# MxxxCol.net
KiCad netlist of a schematic drawn in EAGLE
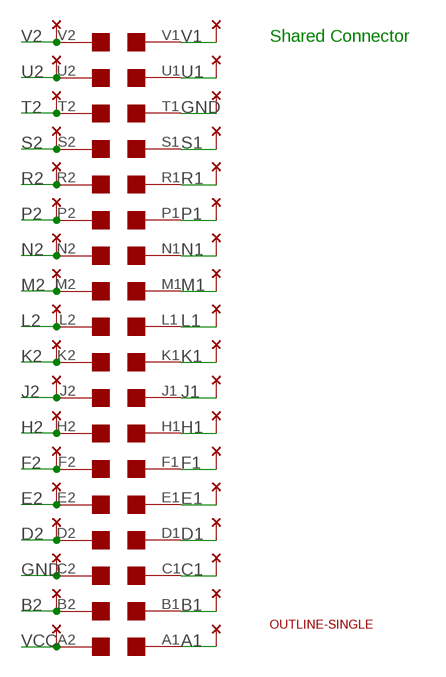
[diagram p0: schematic, sheet 1]
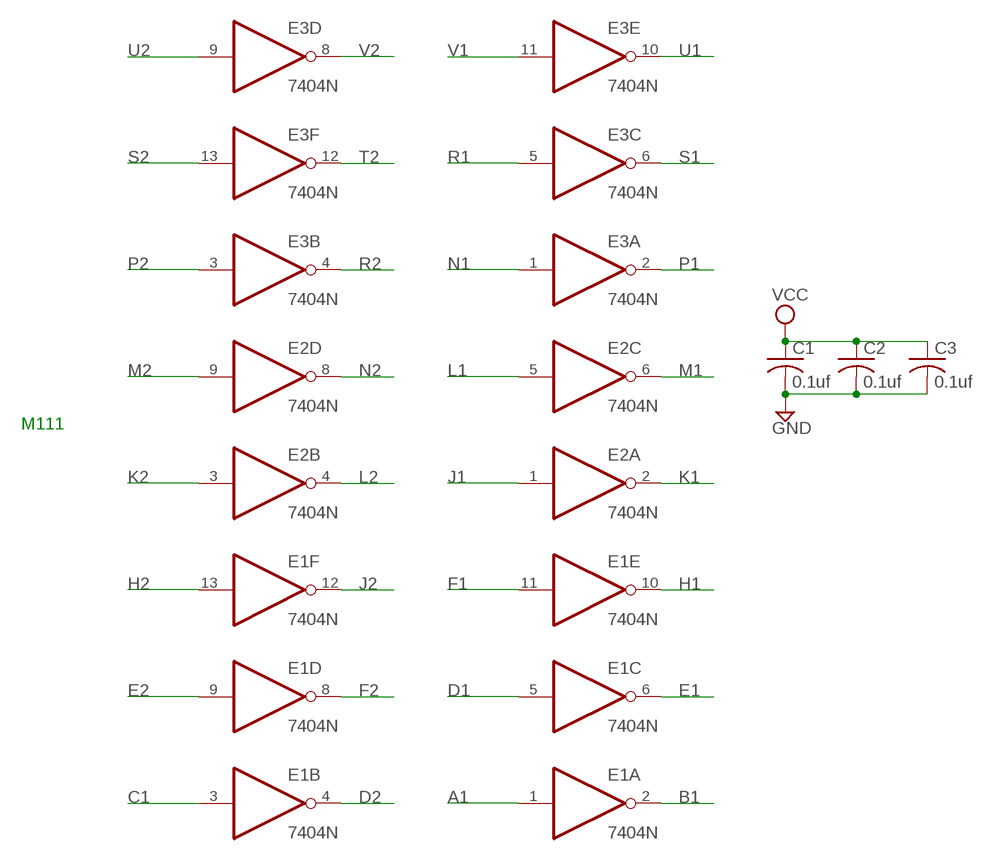
[diagram p1: schematic, sheet 2]
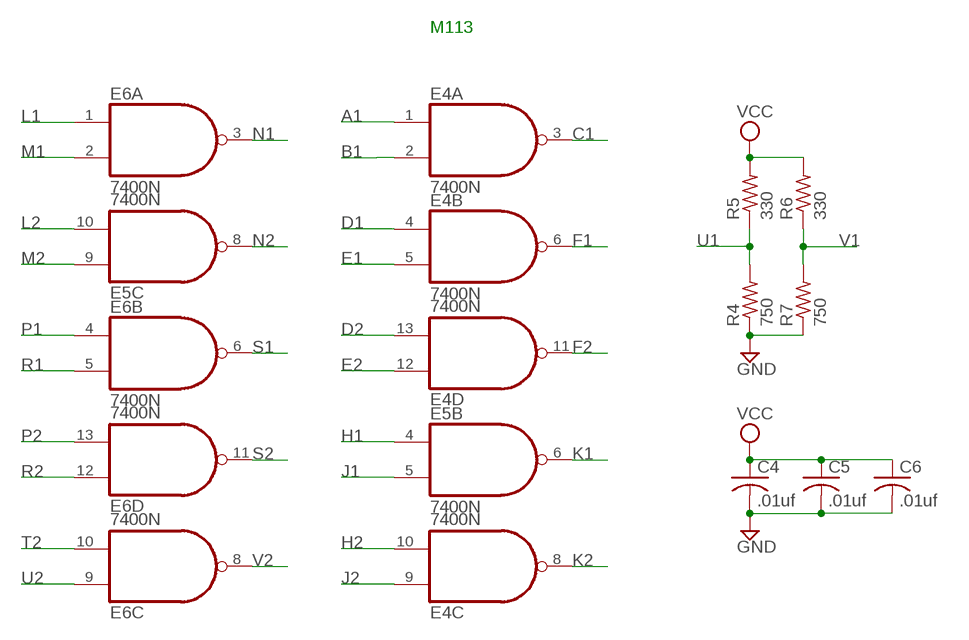
[diagram p2: schematic, sheet 3]
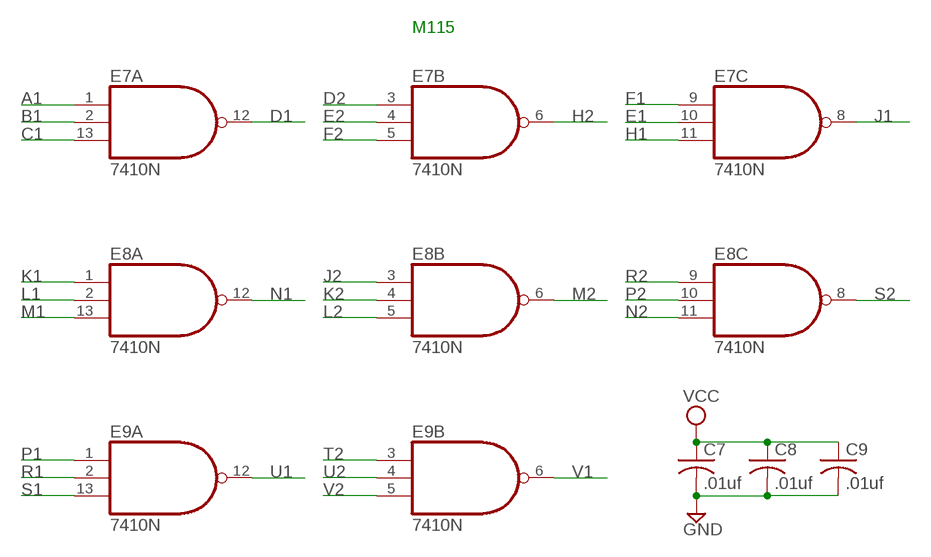
[diagram p3: schematic, sheet 4]
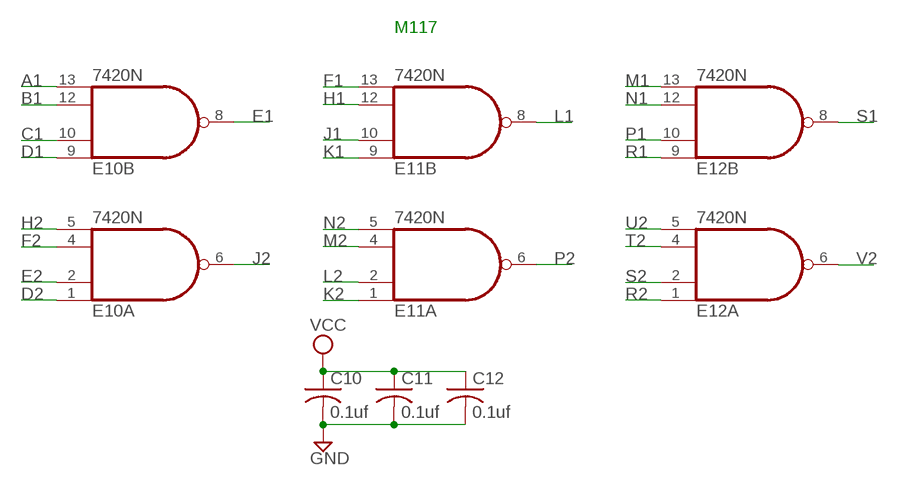
[diagram p4: schematic, sheet 5]
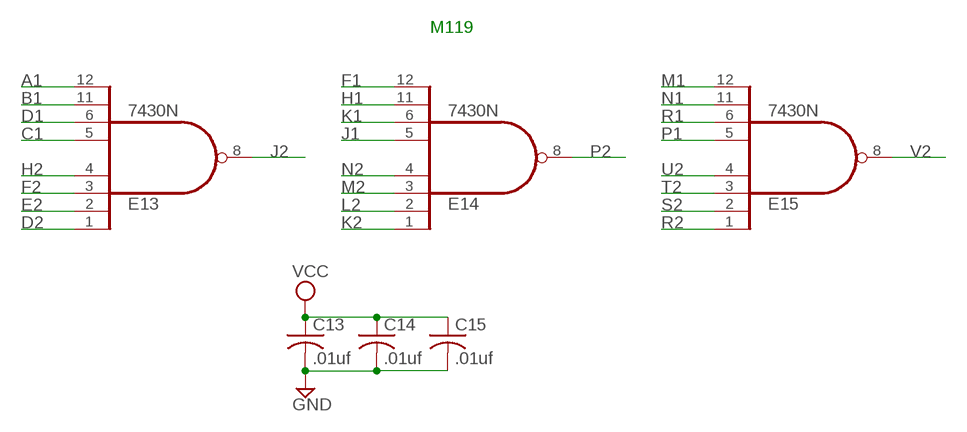
[diagram p5: schematic, sheet 6]

(export (version "E")
  (design (tool "Eeschema 10.0.6"))
  (components
    (comp (ref "U$1")
      (value "EDGE-2CONNECTOR")
      (footprint "eagle-import:EDGE-CON2")
      (libsource (lib "eagle-import") (part "EDGE-2CONNECTOR"))
    )
    (comp (ref "U$2")
      (value "OUTLINE-SINGLE")
      (footprint "eagle-import:SINGLE")
      (libsource (lib "eagle-import") (part "OUTLINE-SINGLE"))
    )
    (comp (ref "U$4")
      (value "THRU-HOLE2A")
      (footprint "eagle-import:THRU-HOLEA")
      (libsource (lib "eagle-import") (part "THRU-HOLE2A"))
    )
    (comp (ref "C7")
      (value ".01uf")
      (footprint "eagle-import:C050-025X075")
      (libsource (lib "eagle-import") (part "C-US050-025X075"))
    )
    (comp (ref "C8")
      (value ".01uf")
      (footprint "eagle-import:C050-025X075")
      (libsource (lib "eagle-import") (part "C-US050-025X075"))
    )
    (comp (ref "C9")
      (value ".01uf")
      (footprint "eagle-import:C050-025X075")
      (libsource (lib "eagle-import") (part "C-US050-025X075"))
    )
    (comp (ref "E7")
      (value "7410N")
      (footprint "eagle-import:DIL14")
      (libsource (lib "eagle-import") (part "7410N"))
    )
    (comp (ref "E8")
      (value "7410N")
      (footprint "eagle-import:DIL14")
      (libsource (lib "eagle-import") (part "7410N"))
    )
    (comp (ref "E9")
      (value "7410N")
      (footprint "eagle-import:DIL14")
      (libsource (lib "eagle-import") (part "7410N"))
    )
    (comp (ref "C4")
      (value ".01uf")
      (footprint "eagle-import:C050-025X075")
      (libsource (lib "eagle-import") (part "C-US050-025X075"))
    )
    (comp (ref "C5")
      (value ".01uf")
      (footprint "eagle-import:C050-025X075")
      (libsource (lib "eagle-import") (part "C-US050-025X075"))
    )
    (comp (ref "C6")
      (value ".01uf")
      (footprint "eagle-import:C050-025X075")
      (libsource (lib "eagle-import") (part "C-US050-025X075"))
    )
    (comp (ref "E4")
      (value "7400N")
      (footprint "eagle-import:DIL14")
      (libsource (lib "eagle-import") (part "7400N"))
    )
    (comp (ref "E5")
      (value "7400N")
      (footprint "eagle-import:DIL14")
      (libsource (lib "eagle-import") (part "7400N"))
    )
    (comp (ref "E6")
      (value "7400N")
      (footprint "eagle-import:DIL14")
      (libsource (lib "eagle-import") (part "7400N"))
    )
    (comp (ref "R4")
      (value "750")
      (footprint "eagle-import:0207_10")
      (libsource (lib "eagle-import") (part "R-US_0207/10"))
    )
    (comp (ref "R5")
      (value "330")
      (footprint "eagle-import:0207_10")
      (libsource (lib "eagle-import") (part "R-US_0207/10"))
    )
    (comp (ref "R6")
      (value "330")
      (footprint "eagle-import:0207_10")
      (libsource (lib "eagle-import") (part "R-US_0207/10"))
    )
    (comp (ref "R7")
      (value "750")
      (footprint "eagle-import:0207_10")
      (libsource (lib "eagle-import") (part "R-US_0207/10"))
    )
    (comp (ref "C13")
      (value ".01uf")
      (footprint "eagle-import:C050-025X075")
      (libsource (lib "eagle-import") (part "C-US050-025X075"))
    )
    (comp (ref "C14")
      (value ".01uf")
      (footprint "eagle-import:C050-025X075")
      (libsource (lib "eagle-import") (part "C-US050-025X075"))
    )
    (comp (ref "C15")
      (value ".01uf")
      (footprint "eagle-import:C050-025X075")
      (libsource (lib "eagle-import") (part "C-US050-025X075"))
    )
    (comp (ref "E13")
      (value "7430N")
      (footprint "eagle-import:DIL14")
      (libsource (lib "eagle-import") (part "7430N"))
    )
    (comp (ref "E14")
      (value "7430N")
      (footprint "eagle-import:DIL14")
      (libsource (lib "eagle-import") (part "7430N"))
    )
    (comp (ref "E15")
      (value "7430N")
      (footprint "eagle-import:DIL14")
      (libsource (lib "eagle-import") (part "7430N"))
    )
    (comp (ref "C1")
      (value "0.1uf")
      (footprint "eagle-import:C050-025X075")
      (libsource (lib "eagle-import") (part "C-US050-025X075"))
    )
    (comp (ref "C2")
      (value "0.1uf")
      (footprint "eagle-import:C050-025X075")
      (libsource (lib "eagle-import") (part "C-US050-025X075"))
    )
    (comp (ref "C3")
      (value "0.1uf")
      (footprint "eagle-import:C050-025X075")
      (libsource (lib "eagle-import") (part "C-US050-025X075"))
    )
    (comp (ref "E1")
      (value "7404N")
      (footprint "eagle-import:DIL14")
      (libsource (lib "eagle-import") (part "7404N"))
    )
    (comp (ref "E2")
      (value "7404N")
      (footprint "eagle-import:DIL14")
      (libsource (lib "eagle-import") (part "7404N"))
    )
    (comp (ref "E3")
      (value "7404N")
      (footprint "eagle-import:DIL14")
      (libsource (lib "eagle-import") (part "7404N"))
    )
    (comp (ref "C10")
      (value "0.1uf")
      (footprint "eagle-import:C050-025X075")
      (libsource (lib "eagle-import") (part "C-US050-025X075"))
    )
    (comp (ref "C11")
      (value "0.1uf")
      (footprint "eagle-import:C050-025X075")
      (libsource (lib "eagle-import") (part "C-US050-025X075"))
    )
    (comp (ref "C12")
      (value "0.1uf")
      (footprint "eagle-import:C050-025X075")
      (libsource (lib "eagle-import") (part "C-US050-025X075"))
    )
    (comp (ref "E10")
      (value "7420N")
      (footprint "eagle-import:DIL14")
      (libsource (lib "eagle-import") (part "7420NS"))
    )
    (comp (ref "E11")
      (value "7420N")
      (footprint "eagle-import:DIL14")
      (libsource (lib "eagle-import") (part "7420NS"))
    )
    (comp (ref "E12")
      (value "7420N")
      (footprint "eagle-import:DIL14")
      (libsource (lib "eagle-import") (part "7420NS"))
    )
  )
  (nets
    (net (code "1") (name "A1") (class "Default")
      (node (ref "E1") (pin "1") (pinfunction "I_1") (pintype "input"))
      (node (ref "E10") (pin "13") (pinfunction "I3_13") (pintype "input"))
      (node (ref "E13") (pin "12") (pinfunction "I7_12") (pintype "input"))
      (node (ref "E4") (pin "1") (pinfunction "I0_1") (pintype "input"))
      (node (ref "E7") (pin "1") (pinfunction "I0_1") (pintype "input"))
      (node (ref "U$1") (pin "A1") (pinfunction "1_A1") (pintype "bidirectional"))
      (node (ref "U$4") (pin "A1") (pinfunction "P$1_A1") (pintype "passive"))
    )
    (net (code "2") (name "B1") (class "Default")
      (node (ref "E1") (pin "2") (pinfunction "O_2") (pintype "output"))
      (node (ref "E10") (pin "12") (pinfunction "I2_12") (pintype "input"))
      (node (ref "E13") (pin "11") (pinfunction "I6_11") (pintype "input"))
      (node (ref "E4") (pin "2") (pinfunction "I1_2") (pintype "input"))
      (node (ref "E7") (pin "2") (pinfunction "I1_2") (pintype "input"))
      (node (ref "U$1") (pin "B1") (pinfunction "1_B1") (pintype "bidirectional"))
      (node (ref "U$4") (pin "B1") (pinfunction "P$1_B1") (pintype "passive"))
    )
    (net (code "3") (name "B2") (class "Default")
      (node (ref "U$1") (pin "B2") (pinfunction "1_B2") (pintype "bidirectional"))
      (node (ref "U$4") (pin "B2") (pinfunction "P$1_B2") (pintype "passive"))
    )
    (net (code "4") (name "C1") (class "Default")
      (node (ref "E1") (pin "3") (pinfunction "I_3") (pintype "input"))
      (node (ref "E10") (pin "10") (pinfunction "I1_10") (pintype "input"))
      (node (ref "E13") (pin "5") (pinfunction "I4_5") (pintype "input"))
      (node (ref "E4") (pin "3") (pinfunction "O_3") (pintype "output"))
      (node (ref "E7") (pin "13") (pinfunction "I2_13") (pintype "input"))
      (node (ref "U$1") (pin "C1") (pinfunction "1_C1") (pintype "bidirectional"))
      (node (ref "U$4") (pin "C1") (pinfunction "P$1_C1") (pintype "passive"))
    )
    (net (code "5") (name "D1") (class "Default")
      (node (ref "E1") (pin "5") (pinfunction "I_5") (pintype "input"))
      (node (ref "E10") (pin "9") (pinfunction "I0_9") (pintype "input"))
      (node (ref "E13") (pin "6") (pinfunction "I5_6") (pintype "input"))
      (node (ref "E4") (pin "4") (pinfunction "I0_4") (pintype "input"))
      (node (ref "E7") (pin "12") (pinfunction "O_12") (pintype "output"))
      (node (ref "U$1") (pin "D1") (pinfunction "1_D1") (pintype "bidirectional"))
      (node (ref "U$4") (pin "D1") (pinfunction "P$1_D1") (pintype "passive"))
    )
    (net (code "6") (name "D2") (class "Default")
      (node (ref "E1") (pin "4") (pinfunction "O_4") (pintype "output"))
      (node (ref "E10") (pin "1") (pinfunction "I0_1") (pintype "input"))
      (node (ref "E13") (pin "1") (pinfunction "I0_1") (pintype "input"))
      (node (ref "E4") (pin "13") (pinfunction "I1_13") (pintype "input"))
      (node (ref "E7") (pin "3") (pinfunction "I0_3") (pintype "input"))
      (node (ref "U$1") (pin "D2") (pinfunction "1_D2") (pintype "bidirectional"))
      (node (ref "U$4") (pin "D2") (pinfunction "P$1_D2") (pintype "passive"))
    )
    (net (code "7") (name "E1") (class "Default")
      (node (ref "E1") (pin "6") (pinfunction "O_6") (pintype "output"))
      (node (ref "E10") (pin "8") (pinfunction "O_8") (pintype "output"))
      (node (ref "E4") (pin "5") (pinfunction "I1_5") (pintype "input"))
      (node (ref "E7") (pin "10") (pinfunction "I1_10") (pintype "input"))
      (node (ref "U$1") (pin "E1") (pinfunction "1_E1") (pintype "bidirectional"))
      (node (ref "U$4") (pin "E1") (pinfunction "P$1_E1") (pintype "passive"))
    )
    (net (code "8") (name "E2") (class "Default")
      (node (ref "E1") (pin "9") (pinfunction "I_9") (pintype "input"))
      (node (ref "E10") (pin "2") (pinfunction "I1_2") (pintype "input"))
      (node (ref "E13") (pin "2") (pinfunction "I1_2") (pintype "input"))
      (node (ref "E4") (pin "12") (pinfunction "I0_12") (pintype "input"))
      (node (ref "E7") (pin "4") (pinfunction "I1_4") (pintype "input"))
      (node (ref "U$1") (pin "E2") (pinfunction "1_E2") (pintype "bidirectional"))
      (node (ref "U$4") (pin "E2") (pinfunction "P$1_E2") (pintype "passive"))
    )
    (net (code "9") (name "F1") (class "Default")
      (node (ref "E1") (pin "11") (pinfunction "I_11") (pintype "input"))
      (node (ref "E11") (pin "13") (pinfunction "I3_13") (pintype "input"))
      (node (ref "E14") (pin "12") (pinfunction "I7_12") (pintype "input"))
      (node (ref "E4") (pin "6") (pinfunction "O_6") (pintype "output"))
      (node (ref "E7") (pin "9") (pinfunction "I0_9") (pintype "input"))
      (node (ref "U$1") (pin "F1") (pinfunction "1_F1") (pintype "bidirectional"))
      (node (ref "U$4") (pin "F1") (pinfunction "P$1_F1") (pintype "passive"))
    )
    (net (code "10") (name "F2") (class "Default")
      (node (ref "E1") (pin "8") (pinfunction "O_8") (pintype "output"))
      (node (ref "E10") (pin "4") (pinfunction "I2_4") (pintype "input"))
      (node (ref "E13") (pin "3") (pinfunction "I2_3") (pintype "input"))
      (node (ref "E4") (pin "11") (pinfunction "O_11") (pintype "output"))
      (node (ref "E7") (pin "5") (pinfunction "I2_5") (pintype "input"))
      (node (ref "U$1") (pin "F2") (pinfunction "1_F2") (pintype "bidirectional"))
      (node (ref "U$4") (pin "F2") (pinfunction "P$1_F2") (pintype "passive"))
    )
    (net (code "11") (name "GND") (class "Default")
      (node (ref "C1") (pin "2") (pinfunction "2_2") (pintype "passive"))
      (node (ref "C10") (pin "2") (pinfunction "2_2") (pintype "passive"))
      (node (ref "C11") (pin "2") (pinfunction "2_2") (pintype "passive"))
      (node (ref "C12") (pin "2") (pinfunction "2_2") (pintype "passive"))
      (node (ref "C13") (pin "2") (pinfunction "2_2") (pintype "passive"))
      (node (ref "C14") (pin "2") (pinfunction "2_2") (pintype "passive"))
      (node (ref "C15") (pin "2") (pinfunction "2_2") (pintype "passive"))
      (node (ref "C2") (pin "2") (pinfunction "2_2") (pintype "passive"))
      (node (ref "C3") (pin "2") (pinfunction "2_2") (pintype "passive"))
      (node (ref "C4") (pin "2") (pinfunction "2_2") (pintype "passive"))
      (node (ref "C5") (pin "2") (pinfunction "2_2") (pintype "passive"))
      (node (ref "C6") (pin "2") (pinfunction "2_2") (pintype "passive"))
      (node (ref "C7") (pin "2") (pinfunction "2_2") (pintype "passive"))
      (node (ref "C8") (pin "2") (pinfunction "2_2") (pintype "passive"))
      (node (ref "C9") (pin "2") (pinfunction "2_2") (pintype "passive"))
      (node (ref "R4") (pin "1") (pinfunction "1_1") (pintype "passive"))
      (node (ref "R7") (pin "1") (pinfunction "1_1") (pintype "passive"))
      (node (ref "U$1") (pin "C2") (pinfunction "1_C2") (pintype "bidirectional"))
      (node (ref "U$1") (pin "T1") (pinfunction "1_T1") (pintype "bidirectional"))
      (node (ref "U$4") (pin "C2") (pinfunction "P$1_C2") (pintype "passive"))
      (node (ref "U$4") (pin "T1") (pinfunction "P$1_T1") (pintype "passive"))
    )
    (net (code "12") (name "H1") (class "Default")
      (node (ref "E1") (pin "10") (pinfunction "O_10") (pintype "output"))
      (node (ref "E11") (pin "12") (pinfunction "I2_12") (pintype "input"))
      (node (ref "E14") (pin "11") (pinfunction "I6_11") (pintype "input"))
      (node (ref "E5") (pin "4") (pinfunction "I0_4") (pintype "input"))
      (node (ref "E7") (pin "11") (pinfunction "I2_11") (pintype "input"))
      (node (ref "U$1") (pin "H1") (pinfunction "1_H1") (pintype "bidirectional"))
      (node (ref "U$4") (pin "H1") (pinfunction "P$1_H1") (pintype "passive"))
    )
    (net (code "13") (name "H2") (class "Default")
      (node (ref "E1") (pin "13") (pinfunction "I_13") (pintype "input"))
      (node (ref "E10") (pin "5") (pinfunction "I3_5") (pintype "input"))
      (node (ref "E13") (pin "4") (pinfunction "I3_4") (pintype "input"))
      (node (ref "E4") (pin "10") (pinfunction "I1_10") (pintype "input"))
      (node (ref "E7") (pin "6") (pinfunction "O_6") (pintype "output"))
      (node (ref "U$1") (pin "H2") (pinfunction "1_H2") (pintype "bidirectional"))
      (node (ref "U$4") (pin "H2") (pinfunction "P$1_H2") (pintype "passive"))
    )
    (net (code "14") (name "J1") (class "Default")
      (node (ref "E11") (pin "10") (pinfunction "I1_10") (pintype "input"))
      (node (ref "E14") (pin "5") (pinfunction "I4_5") (pintype "input"))
      (node (ref "E2") (pin "1") (pinfunction "I_1") (pintype "input"))
      (node (ref "E5") (pin "5") (pinfunction "I1_5") (pintype "input"))
      (node (ref "E7") (pin "8") (pinfunction "O_8") (pintype "output"))
      (node (ref "U$1") (pin "J1") (pinfunction "1_J1") (pintype "bidirectional"))
      (node (ref "U$4") (pin "J1") (pinfunction "P$1_J1") (pintype "passive"))
    )
    (net (code "15") (name "J2") (class "Default")
      (node (ref "E1") (pin "12") (pinfunction "O_12") (pintype "output"))
      (node (ref "E10") (pin "6") (pinfunction "O_6") (pintype "output"))
      (node (ref "E13") (pin "8") (pinfunction "O_8") (pintype "output"))
      (node (ref "E4") (pin "9") (pinfunction "I0_9") (pintype "input"))
      (node (ref "E8") (pin "3") (pinfunction "I0_3") (pintype "input"))
      (node (ref "U$1") (pin "J2") (pinfunction "1_J2") (pintype "bidirectional"))
      (node (ref "U$4") (pin "J2") (pinfunction "P$1_J2") (pintype "passive"))
    )
    (net (code "16") (name "K1") (class "Default")
      (node (ref "E11") (pin "9") (pinfunction "I0_9") (pintype "input"))
      (node (ref "E14") (pin "6") (pinfunction "I5_6") (pintype "input"))
      (node (ref "E2") (pin "2") (pinfunction "O_2") (pintype "output"))
      (node (ref "E5") (pin "6") (pinfunction "O_6") (pintype "output"))
      (node (ref "E8") (pin "1") (pinfunction "I0_1") (pintype "input"))
      (node (ref "U$1") (pin "K1") (pinfunction "1_K1") (pintype "bidirectional"))
      (node (ref "U$4") (pin "K1") (pinfunction "P$1_K1") (pintype "passive"))
    )
    (net (code "17") (name "K2") (class "Default")
      (node (ref "E11") (pin "1") (pinfunction "I0_1") (pintype "input"))
      (node (ref "E14") (pin "1") (pinfunction "I0_1") (pintype "input"))
      (node (ref "E2") (pin "3") (pinfunction "I_3") (pintype "input"))
      (node (ref "E4") (pin "8") (pinfunction "O_8") (pintype "output"))
      (node (ref "E8") (pin "4") (pinfunction "I1_4") (pintype "input"))
      (node (ref "U$1") (pin "K2") (pinfunction "1_K2") (pintype "bidirectional"))
      (node (ref "U$4") (pin "K2") (pinfunction "P$1_K2") (pintype "passive"))
    )
    (net (code "18") (name "L1") (class "Default")
      (node (ref "E11") (pin "8") (pinfunction "O_8") (pintype "output"))
      (node (ref "E2") (pin "5") (pinfunction "I_5") (pintype "input"))
      (node (ref "E6") (pin "1") (pinfunction "I0_1") (pintype "input"))
      (node (ref "E8") (pin "2") (pinfunction "I1_2") (pintype "input"))
      (node (ref "U$1") (pin "L1") (pinfunction "1_L1") (pintype "bidirectional"))
      (node (ref "U$4") (pin "L1") (pinfunction "P$1_L1") (pintype "passive"))
    )
    (net (code "19") (name "L2") (class "Default")
      (node (ref "E11") (pin "2") (pinfunction "I1_2") (pintype "input"))
      (node (ref "E14") (pin "2") (pinfunction "I1_2") (pintype "input"))
      (node (ref "E2") (pin "4") (pinfunction "O_4") (pintype "output"))
      (node (ref "E5") (pin "10") (pinfunction "I1_10") (pintype "input"))
      (node (ref "E8") (pin "5") (pinfunction "I2_5") (pintype "input"))
      (node (ref "U$1") (pin "L2") (pinfunction "1_L2") (pintype "bidirectional"))
      (node (ref "U$4") (pin "L2") (pinfunction "P$1_L2") (pintype "passive"))
    )
    (net (code "20") (name "M1") (class "Default")
      (node (ref "E12") (pin "13") (pinfunction "I3_13") (pintype "input"))
      (node (ref "E15") (pin "12") (pinfunction "I7_12") (pintype "input"))
      (node (ref "E2") (pin "6") (pinfunction "O_6") (pintype "output"))
      (node (ref "E6") (pin "2") (pinfunction "I1_2") (pintype "input"))
      (node (ref "E8") (pin "13") (pinfunction "I2_13") (pintype "input"))
      (node (ref "U$1") (pin "M1") (pinfunction "1_M1") (pintype "bidirectional"))
      (node (ref "U$4") (pin "M1") (pinfunction "P$1_M1") (pintype "passive"))
    )
    (net (code "21") (name "M2") (class "Default")
      (node (ref "E11") (pin "4") (pinfunction "I2_4") (pintype "input"))
      (node (ref "E14") (pin "3") (pinfunction "I2_3") (pintype "input"))
      (node (ref "E2") (pin "9") (pinfunction "I_9") (pintype "input"))
      (node (ref "E5") (pin "9") (pinfunction "I0_9") (pintype "input"))
      (node (ref "E8") (pin "6") (pinfunction "O_6") (pintype "output"))
      (node (ref "U$1") (pin "M2") (pinfunction "1_M2") (pintype "bidirectional"))
      (node (ref "U$4") (pin "M2") (pinfunction "P$1_M2") (pintype "passive"))
    )
    (net (code "22") (name "N1") (class "Default")
      (node (ref "E12") (pin "12") (pinfunction "I2_12") (pintype "input"))
      (node (ref "E15") (pin "11") (pinfunction "I6_11") (pintype "input"))
      (node (ref "E3") (pin "1") (pinfunction "I_1") (pintype "input"))
      (node (ref "E6") (pin "3") (pinfunction "O_3") (pintype "output"))
      (node (ref "E8") (pin "12") (pinfunction "O_12") (pintype "output"))
      (node (ref "U$1") (pin "N1") (pinfunction "1_N1") (pintype "bidirectional"))
      (node (ref "U$4") (pin "N1") (pinfunction "P$1_N1") (pintype "passive"))
    )
    (net (code "23") (name "N2") (class "Default")
      (node (ref "E11") (pin "5") (pinfunction "I3_5") (pintype "input"))
      (node (ref "E14") (pin "4") (pinfunction "I3_4") (pintype "input"))
      (node (ref "E2") (pin "8") (pinfunction "O_8") (pintype "output"))
      (node (ref "E5") (pin "8") (pinfunction "O_8") (pintype "output"))
      (node (ref "E8") (pin "11") (pinfunction "I2_11") (pintype "input"))
      (node (ref "U$1") (pin "N2") (pinfunction "1_N2") (pintype "bidirectional"))
      (node (ref "U$4") (pin "N2") (pinfunction "P$1_N2") (pintype "passive"))
    )
    (net (code "24") (name "P1") (class "Default")
      (node (ref "E12") (pin "10") (pinfunction "I1_10") (pintype "input"))
      (node (ref "E15") (pin "5") (pinfunction "I4_5") (pintype "input"))
      (node (ref "E3") (pin "2") (pinfunction "O_2") (pintype "output"))
      (node (ref "E6") (pin "4") (pinfunction "I0_4") (pintype "input"))
      (node (ref "E9") (pin "1") (pinfunction "I0_1") (pintype "input"))
      (node (ref "U$1") (pin "P1") (pinfunction "1_P1") (pintype "bidirectional"))
      (node (ref "U$4") (pin "P1") (pinfunction "P$1_P1") (pintype "passive"))
    )
    (net (code "25") (name "P2") (class "Default")
      (node (ref "E11") (pin "6") (pinfunction "O_6") (pintype "output"))
      (node (ref "E14") (pin "8") (pinfunction "O_8") (pintype "output"))
      (node (ref "E3") (pin "3") (pinfunction "I_3") (pintype "input"))
      (node (ref "E6") (pin "13") (pinfunction "I1_13") (pintype "input"))
      (node (ref "E8") (pin "10") (pinfunction "I1_10") (pintype "input"))
      (node (ref "U$1") (pin "P2") (pinfunction "1_P2") (pintype "bidirectional"))
      (node (ref "U$4") (pin "P2") (pinfunction "P$1_P2") (pintype "passive"))
    )
    (net (code "26") (name "R1") (class "Default")
      (node (ref "E12") (pin "9") (pinfunction "I0_9") (pintype "input"))
      (node (ref "E15") (pin "6") (pinfunction "I5_6") (pintype "input"))
      (node (ref "E3") (pin "5") (pinfunction "I_5") (pintype "input"))
      (node (ref "E6") (pin "5") (pinfunction "I1_5") (pintype "input"))
      (node (ref "E9") (pin "2") (pinfunction "I1_2") (pintype "input"))
      (node (ref "U$1") (pin "R1") (pinfunction "1_R1") (pintype "bidirectional"))
      (node (ref "U$4") (pin "R1") (pinfunction "P$1_R1") (pintype "passive"))
    )
    (net (code "27") (name "R2") (class "Default")
      (node (ref "E12") (pin "1") (pinfunction "I0_1") (pintype "input"))
      (node (ref "E15") (pin "1") (pinfunction "I0_1") (pintype "input"))
      (node (ref "E3") (pin "4") (pinfunction "O_4") (pintype "output"))
      (node (ref "E6") (pin "12") (pinfunction "I0_12") (pintype "input"))
      (node (ref "E8") (pin "9") (pinfunction "I0_9") (pintype "input"))
      (node (ref "U$1") (pin "R2") (pinfunction "1_R2") (pintype "bidirectional"))
      (node (ref "U$4") (pin "R2") (pinfunction "P$1_R2") (pintype "passive"))
    )
    (net (code "28") (name "S1") (class "Default")
      (node (ref "E12") (pin "8") (pinfunction "O_8") (pintype "output"))
      (node (ref "E3") (pin "6") (pinfunction "O_6") (pintype "output"))
      (node (ref "E6") (pin "6") (pinfunction "O_6") (pintype "output"))
      (node (ref "E9") (pin "13") (pinfunction "I2_13") (pintype "input"))
      (node (ref "U$1") (pin "S1") (pinfunction "1_S1") (pintype "bidirectional"))
      (node (ref "U$4") (pin "S1") (pinfunction "P$1_S1") (pintype "passive"))
    )
    (net (code "29") (name "S2") (class "Default")
      (node (ref "E12") (pin "2") (pinfunction "I1_2") (pintype "input"))
      (node (ref "E15") (pin "2") (pinfunction "I1_2") (pintype "input"))
      (node (ref "E3") (pin "13") (pinfunction "I_13") (pintype "input"))
      (node (ref "E6") (pin "11") (pinfunction "O_11") (pintype "output"))
      (node (ref "E8") (pin "8") (pinfunction "O_8") (pintype "output"))
      (node (ref "U$1") (pin "S2") (pinfunction "1_S2") (pintype "bidirectional"))
      (node (ref "U$4") (pin "S2") (pinfunction "P$1_S2") (pintype "passive"))
    )
    (net (code "30") (name "T2") (class "Default")
      (node (ref "E12") (pin "4") (pinfunction "I2_4") (pintype "input"))
      (node (ref "E15") (pin "3") (pinfunction "I2_3") (pintype "input"))
      (node (ref "E3") (pin "12") (pinfunction "O_12") (pintype "output"))
      (node (ref "E6") (pin "10") (pinfunction "I1_10") (pintype "input"))
      (node (ref "E9") (pin "3") (pinfunction "I0_3") (pintype "input"))
      (node (ref "U$1") (pin "T2") (pinfunction "1_T2") (pintype "bidirectional"))
      (node (ref "U$4") (pin "T2") (pinfunction "P$1_T2") (pintype "passive"))
    )
    (net (code "31") (name "U1") (class "Default")
      (node (ref "E3") (pin "10") (pinfunction "O_10") (pintype "output"))
      (node (ref "E9") (pin "12") (pinfunction "O_12") (pintype "output"))
      (node (ref "R4") (pin "2") (pinfunction "2_2") (pintype "passive"))
      (node (ref "R5") (pin "1") (pinfunction "1_1") (pintype "passive"))
      (node (ref "U$1") (pin "U1") (pinfunction "1_U1") (pintype "bidirectional"))
      (node (ref "U$4") (pin "U1") (pinfunction "P$1_U1") (pintype "passive"))
    )
    (net (code "32") (name "U2") (class "Default")
      (node (ref "E12") (pin "5") (pinfunction "I3_5") (pintype "input"))
      (node (ref "E15") (pin "4") (pinfunction "I3_4") (pintype "input"))
      (node (ref "E3") (pin "9") (pinfunction "I_9") (pintype "input"))
      (node (ref "E6") (pin "9") (pinfunction "I0_9") (pintype "input"))
      (node (ref "E9") (pin "4") (pinfunction "I1_4") (pintype "input"))
      (node (ref "U$1") (pin "U2") (pinfunction "1_U2") (pintype "bidirectional"))
      (node (ref "U$4") (pin "U2") (pinfunction "P$1_U2") (pintype "passive"))
    )
    (net (code "33") (name "V1") (class "Default")
      (node (ref "E3") (pin "11") (pinfunction "I_11") (pintype "input"))
      (node (ref "E9") (pin "6") (pinfunction "O_6") (pintype "output"))
      (node (ref "R6") (pin "1") (pinfunction "1_1") (pintype "passive"))
      (node (ref "R7") (pin "2") (pinfunction "2_2") (pintype "passive"))
      (node (ref "U$1") (pin "V1") (pinfunction "1_V1") (pintype "bidirectional"))
      (node (ref "U$4") (pin "V1") (pinfunction "P$1_V1") (pintype "passive"))
    )
    (net (code "34") (name "V2") (class "Default")
      (node (ref "E12") (pin "6") (pinfunction "O_6") (pintype "output"))
      (node (ref "E15") (pin "8") (pinfunction "O_8") (pintype "output"))
      (node (ref "E3") (pin "8") (pinfunction "O_8") (pintype "output"))
      (node (ref "E6") (pin "8") (pinfunction "O_8") (pintype "output"))
      (node (ref "E9") (pin "5") (pinfunction "I2_5") (pintype "input"))
      (node (ref "U$1") (pin "V2") (pinfunction "1_V2") (pintype "bidirectional"))
      (node (ref "U$4") (pin "V2") (pinfunction "P$1_V2") (pintype "passive"))
    )
    (net (code "35") (name "VCC") (class "Default")
      (node (ref "C1") (pin "1") (pinfunction "1_1") (pintype "passive"))
      (node (ref "C10") (pin "1") (pinfunction "1_1") (pintype "passive"))
      (node (ref "C11") (pin "1") (pinfunction "1_1") (pintype "passive"))
      (node (ref "C12") (pin "1") (pinfunction "1_1") (pintype "passive"))
      (node (ref "C13") (pin "1") (pinfunction "1_1") (pintype "passive"))
      (node (ref "C14") (pin "1") (pinfunction "1_1") (pintype "passive"))
      (node (ref "C15") (pin "1") (pinfunction "1_1") (pintype "passive"))
      (node (ref "C2") (pin "1") (pinfunction "1_1") (pintype "passive"))
      (node (ref "C3") (pin "1") (pinfunction "1_1") (pintype "passive"))
      (node (ref "C4") (pin "1") (pinfunction "1_1") (pintype "passive"))
      (node (ref "C5") (pin "1") (pinfunction "1_1") (pintype "passive"))
      (node (ref "C6") (pin "1") (pinfunction "1_1") (pintype "passive"))
      (node (ref "C7") (pin "1") (pinfunction "1_1") (pintype "passive"))
      (node (ref "C8") (pin "1") (pinfunction "1_1") (pintype "passive"))
      (node (ref "C9") (pin "1") (pinfunction "1_1") (pintype "passive"))
      (node (ref "R5") (pin "2") (pinfunction "2_2") (pintype "passive"))
      (node (ref "R6") (pin "2") (pinfunction "2_2") (pintype "passive"))
      (node (ref "U$1") (pin "A2") (pinfunction "1_A2") (pintype "bidirectional"))
      (node (ref "U$4") (pin "A2") (pinfunction "P$1_A2") (pintype "passive"))
    )
  )
)
